# ChristmasTree.net
KiCad netlist of a schematic drawn in EAGLE
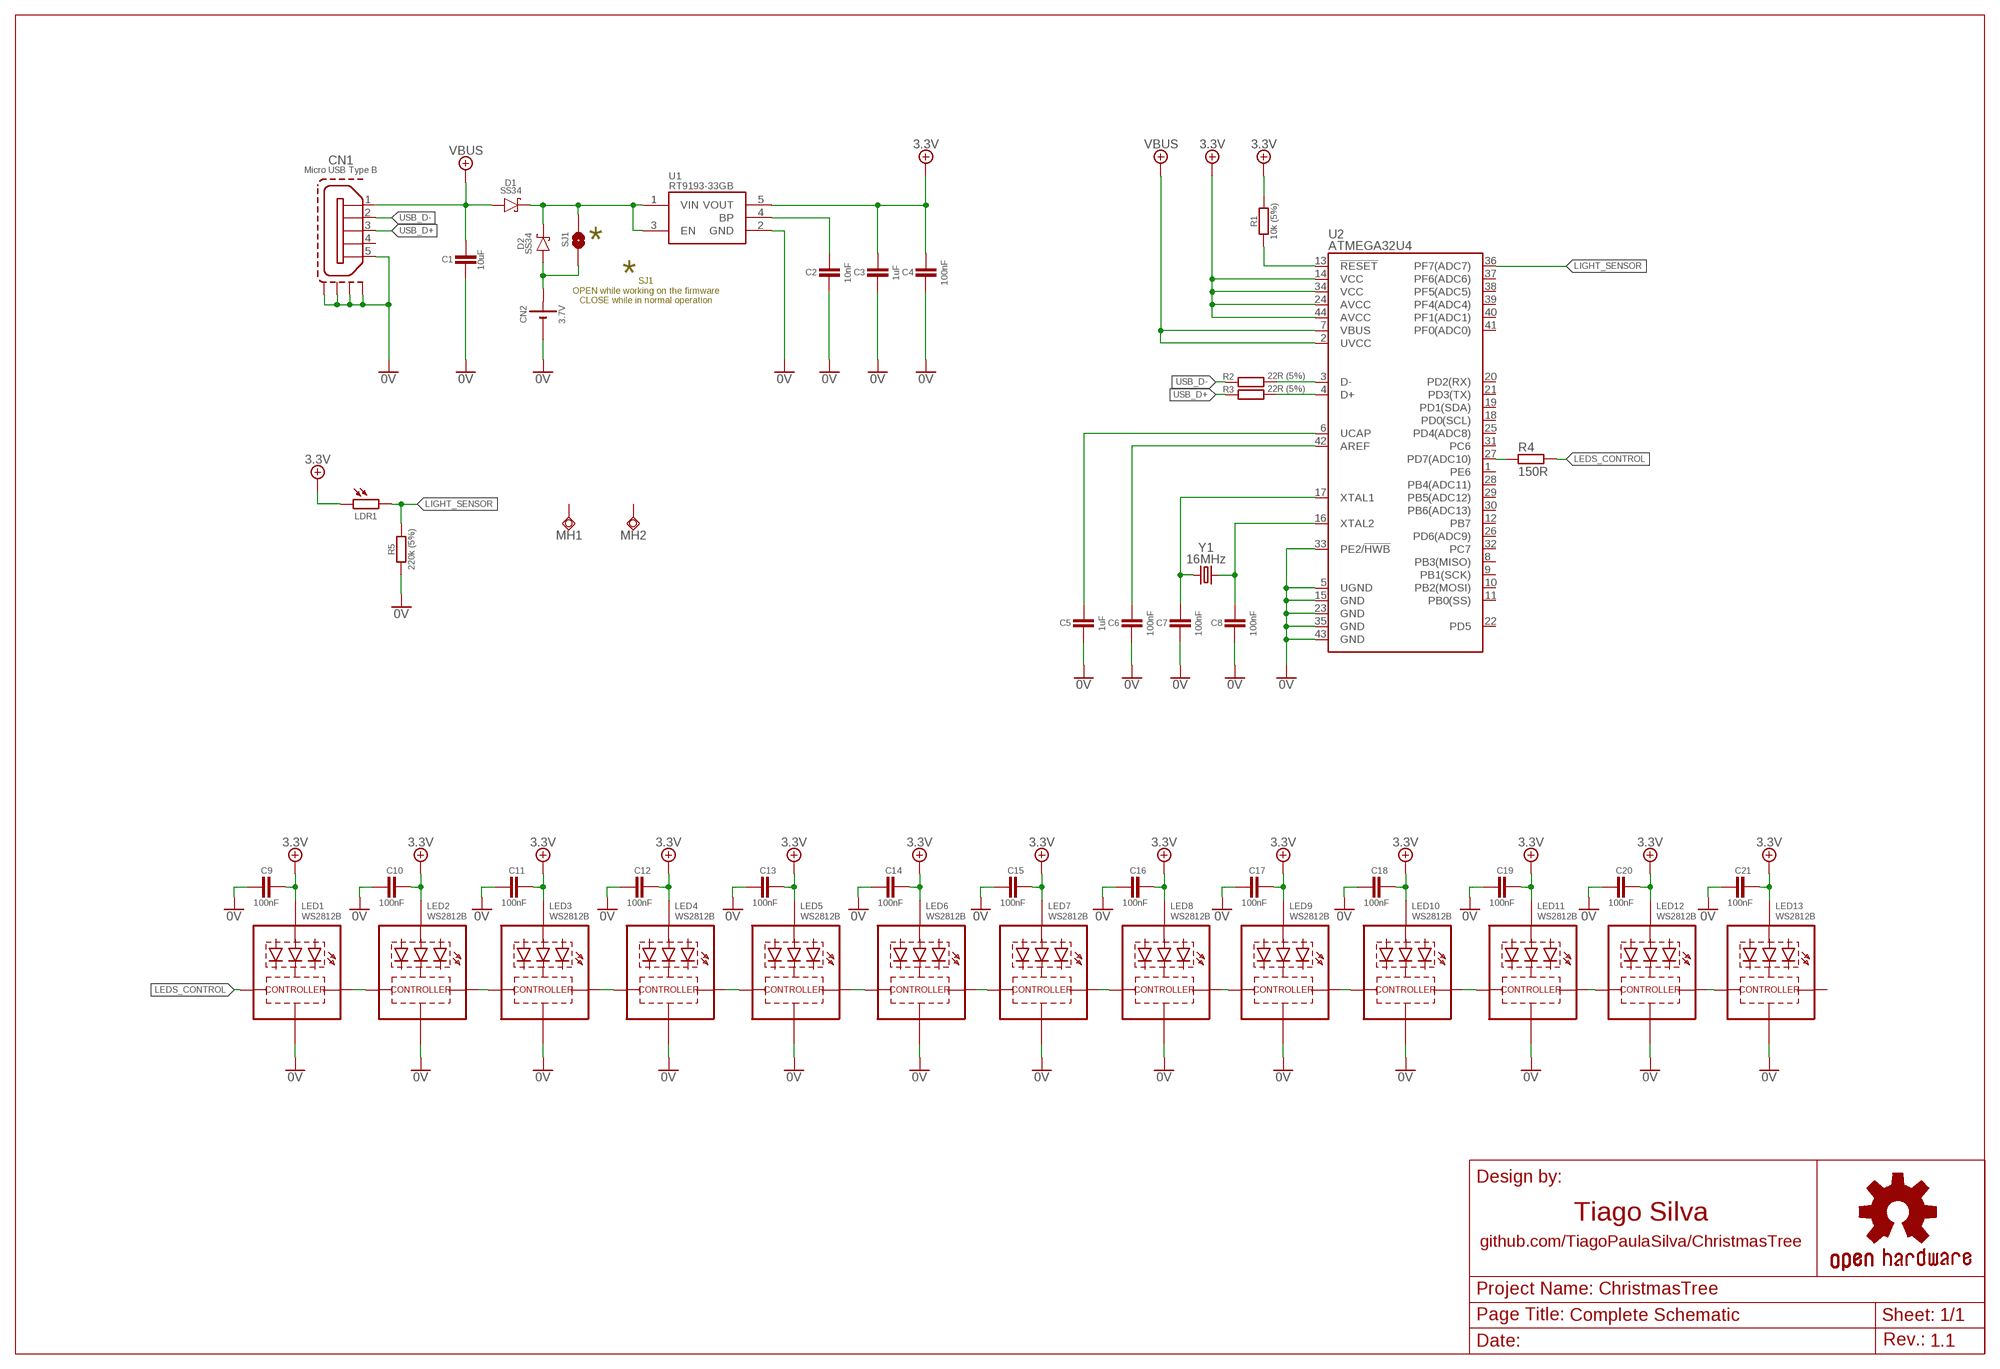
[diagram p0: schematic, sheet 1]

(export (version "E")
  (design (tool "Eeschema 10.0.6"))
  (components
    (comp (ref "C1")
      (value "10uF")
      (footprint "eagle-import:C0805")
      (libsource (lib "eagle-import") (part "C_0805"))
    )
    (comp (ref "C2")
      (value "10nF")
      (footprint "eagle-import:C0603")
      (libsource (lib "eagle-import") (part "C_0603"))
    )
    (comp (ref "C3")
      (value "1uF")
      (footprint "eagle-import:C0603")
      (libsource (lib "eagle-import") (part "C_0603"))
    )
    (comp (ref "C4")
      (value "100nF")
      (footprint "eagle-import:C0603")
      (libsource (lib "eagle-import") (part "C_0603"))
    )
    (comp (ref "C5")
      (value "1uF")
      (footprint "eagle-import:C0603")
      (libsource (lib "eagle-import") (part "C_0603"))
    )
    (comp (ref "C6")
      (value "100nF")
      (footprint "eagle-import:C0603")
      (libsource (lib "eagle-import") (part "C_0603"))
    )
    (comp (ref "C7")
      (value "100nF")
      (footprint "eagle-import:C0603")
      (libsource (lib "eagle-import") (part "C_0603"))
    )
    (comp (ref "C8")
      (value "100nF")
      (footprint "eagle-import:C0603")
      (libsource (lib "eagle-import") (part "C_0603"))
    )
    (comp (ref "C9")
      (value "100nF")
      (footprint "eagle-import:C0603")
      (libsource (lib "eagle-import") (part "C_0603"))
    )
    (comp (ref "C10")
      (value "100nF")
      (footprint "eagle-import:C0603")
      (libsource (lib "eagle-import") (part "C_0603"))
    )
    (comp (ref "C11")
      (value "100nF")
      (footprint "eagle-import:C0603")
      (libsource (lib "eagle-import") (part "C_0603"))
    )
    (comp (ref "C12")
      (value "100nF")
      (footprint "eagle-import:C0603")
      (libsource (lib "eagle-import") (part "C_0603"))
    )
    (comp (ref "C13")
      (value "100nF")
      (footprint "eagle-import:C0603")
      (libsource (lib "eagle-import") (part "C_0603"))
    )
    (comp (ref "C14")
      (value "100nF")
      (footprint "eagle-import:C0603")
      (libsource (lib "eagle-import") (part "C_0603"))
    )
    (comp (ref "C15")
      (value "100nF")
      (footprint "eagle-import:C0603")
      (libsource (lib "eagle-import") (part "C_0603"))
    )
    (comp (ref "C16")
      (value "100nF")
      (footprint "eagle-import:C0603")
      (libsource (lib "eagle-import") (part "C_0603"))
    )
    (comp (ref "C17")
      (value "100nF")
      (footprint "eagle-import:C0603")
      (libsource (lib "eagle-import") (part "C_0603"))
    )
    (comp (ref "C18")
      (value "100nF")
      (footprint "eagle-import:C0603")
      (libsource (lib "eagle-import") (part "C_0603"))
    )
    (comp (ref "C19")
      (value "100nF")
      (footprint "eagle-import:C0603")
      (libsource (lib "eagle-import") (part "C_0603"))
    )
    (comp (ref "C20")
      (value "100nF")
      (footprint "eagle-import:C0603")
      (libsource (lib "eagle-import") (part "C_0603"))
    )
    (comp (ref "C21")
      (value "100nF")
      (footprint "eagle-import:C0603")
      (libsource (lib "eagle-import") (part "C_0603"))
    )
    (comp (ref "CN1")
      (value "Micro USB Type B")
      (footprint "eagle-import:10118193-0001LF")
      (libsource (lib "eagle-import") (part "MICRO-USB"))
    )
    (comp (ref "CN2")
      (value "3.7V")
      (footprint "eagle-import:JST-PH2")
      (libsource (lib "eagle-import") (part "CELL-CONNECTOR"))
    )
    (comp (ref "D1")
      (value "SS34")
      (footprint "eagle-import:DO214AB")
      (libsource (lib "eagle-import") (part "SS34"))
    )
    (comp (ref "D2")
      (value "SS34")
      (footprint "eagle-import:DO214AB")
      (libsource (lib "eagle-import") (part "SS34"))
    )
    (comp (ref "LDR1")
      (value "A1050_09")
      (footprint "eagle-import:T0-46-A10XX")
      (libsource (lib "eagle-import") (part "A1050_09"))
    )
    (comp (ref "LED1")
      (value "WS2812B")
      (footprint "eagle-import:5050")
      (libsource (lib "eagle-import") (part "WS2812B"))
    )
    (comp (ref "LED2")
      (value "WS2812B")
      (footprint "eagle-import:5050")
      (libsource (lib "eagle-import") (part "WS2812B"))
    )
    (comp (ref "LED3")
      (value "WS2812B")
      (footprint "eagle-import:5050")
      (libsource (lib "eagle-import") (part "WS2812B"))
    )
    (comp (ref "LED4")
      (value "WS2812B")
      (footprint "eagle-import:5050")
      (libsource (lib "eagle-import") (part "WS2812B"))
    )
    (comp (ref "LED5")
      (value "WS2812B")
      (footprint "eagle-import:5050")
      (libsource (lib "eagle-import") (part "WS2812B"))
    )
    (comp (ref "LED6")
      (value "WS2812B")
      (footprint "eagle-import:5050")
      (libsource (lib "eagle-import") (part "WS2812B"))
    )
    (comp (ref "LED7")
      (value "WS2812B")
      (footprint "eagle-import:5050")
      (libsource (lib "eagle-import") (part "WS2812B"))
    )
    (comp (ref "LED8")
      (value "WS2812B")
      (footprint "eagle-import:5050")
      (libsource (lib "eagle-import") (part "WS2812B"))
    )
    (comp (ref "LED9")
      (value "WS2812B")
      (footprint "eagle-import:5050")
      (libsource (lib "eagle-import") (part "WS2812B"))
    )
    (comp (ref "LED10")
      (value "WS2812B")
      (footprint "eagle-import:5050")
      (libsource (lib "eagle-import") (part "WS2812B"))
    )
    (comp (ref "LED11")
      (value "WS2812B")
      (footprint "eagle-import:5050")
      (libsource (lib "eagle-import") (part "WS2812B"))
    )
    (comp (ref "LED12")
      (value "WS2812B")
      (footprint "eagle-import:5050")
      (libsource (lib "eagle-import") (part "WS2812B"))
    )
    (comp (ref "LED13")
      (value "WS2812B")
      (footprint "eagle-import:5050")
      (libsource (lib "eagle-import") (part "WS2812B"))
    )
    (comp (ref "MH1")
      (value "TPSQTP20R")
      (footprint "eagle-import:TP20R")
      (libsource (lib "eagle-import") (part "TPSQTP20R"))
    )
    (comp (ref "MH2")
      (value "TPSQTP20R")
      (footprint "eagle-import:TP20R")
      (libsource (lib "eagle-import") (part "TPSQTP20R"))
    )
    (comp (ref "R1")
      (value "10k (5%)")
      (footprint "eagle-import:R0603")
      (libsource (lib "eagle-import") (part "R_0603"))
    )
    (comp (ref "R2")
      (value "22R (5%)")
      (footprint "eagle-import:R0603")
      (libsource (lib "eagle-import") (part "R_0603"))
    )
    (comp (ref "R3")
      (value "22R (5%)")
      (footprint "eagle-import:R0603")
      (libsource (lib "eagle-import") (part "R_0603"))
    )
    (comp (ref "R4")
      (value "150R")
      (footprint "eagle-import:R0603")
      (libsource (lib "eagle-import") (part "R_0603"))
    )
    (comp (ref "R5")
      (value "220k (5%)")
      (footprint "eagle-import:R0603")
      (libsource (lib "eagle-import") (part "R_0603"))
    )
    (comp (ref "SJ1") (value "SJ") (footprint "eagle-import:SJ") (libsource (lib "eagle-import") (part "SJ")))
    (comp (ref "U1")
      (value "RT9193-33GB")
      (footprint "eagle-import:SOT94P279X129-5N")
      (fields (field (name "MF") "Richtek USA"))
      (libsource (lib "eagle-import") (part "RT9193-33GB"))
    )
    (comp (ref "U2")
      (value "ATMEGA32U4")
      (footprint "eagle-import:TESTING_QFN-44")
      (libsource (lib "eagle-import") (part "TESTING_ATMEGA32U4QFN"))
    )
    (comp (ref "Y1")
      (value "16MHz")
      (footprint "eagle-import:5.0X3.2_KX-9A")
      (libsource (lib "eagle-import") (part "KX-9A"))
    )
  )
  (nets
    (net (code "1") (name "0V") (class "Default")
      (node (ref "C1") (pin "2") (pinfunction "2_2") (pintype "passive"))
      (node (ref "C10") (pin "2") (pinfunction "2_2") (pintype "passive"))
      (node (ref "C11") (pin "2") (pinfunction "2_2") (pintype "passive"))
      (node (ref "C12") (pin "2") (pinfunction "2_2") (pintype "passive"))
      (node (ref "C13") (pin "2") (pinfunction "2_2") (pintype "passive"))
      (node (ref "C14") (pin "2") (pinfunction "2_2") (pintype "passive"))
      (node (ref "C15") (pin "2") (pinfunction "2_2") (pintype "passive"))
      (node (ref "C16") (pin "2") (pinfunction "2_2") (pintype "passive"))
      (node (ref "C17") (pin "2") (pinfunction "2_2") (pintype "passive"))
      (node (ref "C18") (pin "2") (pinfunction "2_2") (pintype "passive"))
      (node (ref "C19") (pin "2") (pinfunction "2_2") (pintype "passive"))
      (node (ref "C2") (pin "2") (pinfunction "2_2") (pintype "passive"))
      (node (ref "C20") (pin "2") (pinfunction "2_2") (pintype "passive"))
      (node (ref "C21") (pin "2") (pinfunction "2_2") (pintype "passive"))
      (node (ref "C3") (pin "2") (pinfunction "2_2") (pintype "passive"))
      (node (ref "C4") (pin "2") (pinfunction "2_2") (pintype "passive"))
      (node (ref "C5") (pin "2") (pinfunction "2_2") (pintype "passive"))
      (node (ref "C6") (pin "2") (pinfunction "2_2") (pintype "passive"))
      (node (ref "C7") (pin "2") (pinfunction "2_2") (pintype "passive"))
      (node (ref "C8") (pin "2") (pinfunction "2_2") (pintype "passive"))
      (node (ref "C9") (pin "2") (pinfunction "2_2") (pintype "passive"))
      (node (ref "CN1") (pin "5") (pinfunction "5_5") (pintype "passive"))
      (node (ref "CN1") (pin "MP1") (pinfunction "S1_MP1") (pintype "passive"))
      (node (ref "CN1") (pin "MP2") (pinfunction "S2_MP2") (pintype "passive"))
      (node (ref "CN1") (pin "MP3") (pinfunction "S3_MP3") (pintype "passive"))
      (node (ref "CN1") (pin "MP4") (pinfunction "S4_MP4") (pintype "passive"))
      (node (ref "CN2") (pin "2") (pinfunction "-_2") (pintype "passive"))
      (node (ref "LED1") (pin "3-GND") (pinfunction "GND_3-GND") (pintype "power_in"))
      (node (ref "LED10") (pin "3-GND") (pinfunction "GND_3-GND") (pintype "power_in"))
      (node (ref "LED11") (pin "3-GND") (pinfunction "GND_3-GND") (pintype "power_in"))
      (node (ref "LED12") (pin "3-GND") (pinfunction "GND_3-GND") (pintype "power_in"))
      (node (ref "LED13") (pin "3-GND") (pinfunction "GND_3-GND") (pintype "power_in"))
      (node (ref "LED2") (pin "3-GND") (pinfunction "GND_3-GND") (pintype "power_in"))
      (node (ref "LED3") (pin "3-GND") (pinfunction "GND_3-GND") (pintype "power_in"))
      (node (ref "LED4") (pin "3-GND") (pinfunction "GND_3-GND") (pintype "power_in"))
      (node (ref "LED5") (pin "3-GND") (pinfunction "GND_3-GND") (pintype "power_in"))
      (node (ref "LED6") (pin "3-GND") (pinfunction "GND_3-GND") (pintype "power_in"))
      (node (ref "LED7") (pin "3-GND") (pinfunction "GND_3-GND") (pintype "power_in"))
      (node (ref "LED8") (pin "3-GND") (pinfunction "GND_3-GND") (pintype "power_in"))
      (node (ref "LED9") (pin "3-GND") (pinfunction "GND_3-GND") (pintype "power_in"))
      (node (ref "R5") (pin "1") (pinfunction "1_1") (pintype "passive"))
      (node (ref "U1") (pin "2") (pinfunction "GND_2") (pintype "power_in"))
      (node (ref "U2") (pin "15") (pinfunction "GND_15") (pintype "bidirectional"))
      (node (ref "U2") (pin "23") (pinfunction "GND_23") (pintype "bidirectional"))
      (node (ref "U2") (pin "33") (pinfunction "PE2/~{HWB}_33") (pintype "bidirectional"))
      (node (ref "U2") (pin "35") (pinfunction "GND_35") (pintype "bidirectional"))
      (node (ref "U2") (pin "43") (pinfunction "GND_43") (pintype "bidirectional"))
      (node (ref "U2") (pin "5") (pinfunction "UGND_5") (pintype "bidirectional"))
    )
    (net (code "2") (name "3.3V") (class "Default")
      (node (ref "C10") (pin "1") (pinfunction "1_1") (pintype "passive"))
      (node (ref "C11") (pin "1") (pinfunction "1_1") (pintype "passive"))
      (node (ref "C12") (pin "1") (pinfunction "1_1") (pintype "passive"))
      (node (ref "C13") (pin "1") (pinfunction "1_1") (pintype "passive"))
      (node (ref "C14") (pin "1") (pinfunction "1_1") (pintype "passive"))
      (node (ref "C15") (pin "1") (pinfunction "1_1") (pintype "passive"))
      (node (ref "C16") (pin "1") (pinfunction "1_1") (pintype "passive"))
      (node (ref "C17") (pin "1") (pinfunction "1_1") (pintype "passive"))
      (node (ref "C18") (pin "1") (pinfunction "1_1") (pintype "passive"))
      (node (ref "C19") (pin "1") (pinfunction "1_1") (pintype "passive"))
      (node (ref "C20") (pin "1") (pinfunction "1_1") (pintype "passive"))
      (node (ref "C21") (pin "1") (pinfunction "1_1") (pintype "passive"))
      (node (ref "C3") (pin "1") (pinfunction "1_1") (pintype "passive"))
      (node (ref "C4") (pin "1") (pinfunction "1_1") (pintype "passive"))
      (node (ref "C9") (pin "1") (pinfunction "1_1") (pintype "passive"))
      (node (ref "LDR1") (pin "1") (pinfunction "1_1") (pintype "passive"))
      (node (ref "LED1") (pin "1-VDD") (pinfunction "VDD_1-VDD") (pintype "power_in"))
      (node (ref "LED10") (pin "1-VDD") (pinfunction "VDD_1-VDD") (pintype "power_in"))
      (node (ref "LED11") (pin "1-VDD") (pinfunction "VDD_1-VDD") (pintype "power_in"))
      (node (ref "LED12") (pin "1-VDD") (pinfunction "VDD_1-VDD") (pintype "power_in"))
      (node (ref "LED13") (pin "1-VDD") (pinfunction "VDD_1-VDD") (pintype "power_in"))
      (node (ref "LED2") (pin "1-VDD") (pinfunction "VDD_1-VDD") (pintype "power_in"))
      (node (ref "LED3") (pin "1-VDD") (pinfunction "VDD_1-VDD") (pintype "power_in"))
      (node (ref "LED4") (pin "1-VDD") (pinfunction "VDD_1-VDD") (pintype "power_in"))
      (node (ref "LED5") (pin "1-VDD") (pinfunction "VDD_1-VDD") (pintype "power_in"))
      (node (ref "LED6") (pin "1-VDD") (pinfunction "VDD_1-VDD") (pintype "power_in"))
      (node (ref "LED7") (pin "1-VDD") (pinfunction "VDD_1-VDD") (pintype "power_in"))
      (node (ref "LED8") (pin "1-VDD") (pinfunction "VDD_1-VDD") (pintype "power_in"))
      (node (ref "LED9") (pin "1-VDD") (pinfunction "VDD_1-VDD") (pintype "power_in"))
      (node (ref "R1") (pin "2") (pinfunction "2_2") (pintype "passive"))
      (node (ref "U1") (pin "5") (pinfunction "VOUT_5") (pintype "output"))
      (node (ref "U2") (pin "14") (pinfunction "VCC_14") (pintype "bidirectional"))
      (node (ref "U2") (pin "24") (pinfunction "AVCC_24") (pintype "bidirectional"))
      (node (ref "U2") (pin "34") (pinfunction "VCC_34") (pintype "bidirectional"))
      (node (ref "U2") (pin "44") (pinfunction "AVCC_44") (pintype "bidirectional"))
    )
    (net (code "3") (name "LEDS_CONTROL") (class "Default")
      (node (ref "LED1") (pin "4-DIN") (pinfunction "DI_4-DIN") (pintype "input"))
      (node (ref "R4") (pin "2") (pinfunction "2_2") (pintype "passive"))
    )
    (net (code "4") (name "LIGHT_SENSOR") (class "Default")
      (node (ref "LDR1") (pin "2") (pinfunction "2_2") (pintype "passive"))
      (node (ref "R5") (pin "2") (pinfunction "2_2") (pintype "passive"))
      (node (ref "U2") (pin "36") (pinfunction "PF7(ADC7)_36") (pintype "bidirectional"))
    )
    (net (code "5") (name "Net-(CN2-+)") (class "Default")
      (node (ref "CN2") (pin "1") (pinfunction "+_1") (pintype "passive"))
      (node (ref "D2") (pin "A") (pinfunction "A_A") (pintype "passive"))
      (node (ref "SJ1") (pin "1") (pinfunction "1_1") (pintype "passive"))
    )
    (net (code "6") (name "Net-(D1-K)") (class "Default")
      (node (ref "D1") (pin "C") (pinfunction "K_C") (pintype "passive"))
      (node (ref "D2") (pin "C") (pinfunction "K_C") (pintype "passive"))
      (node (ref "SJ1") (pin "2") (pinfunction "2_2") (pintype "passive"))
      (node (ref "U1") (pin "1") (pinfunction "VIN_1") (pintype "input"))
      (node (ref "U1") (pin "3") (pinfunction "EN_3") (pintype "input"))
    )
    (net (code "7") (name "Net-(LED1-DO)") (class "Default")
      (node (ref "LED1") (pin "2-DOUT") (pinfunction "DO_2-DOUT") (pintype "output"))
      (node (ref "LED2") (pin "4-DIN") (pinfunction "DI_4-DIN") (pintype "input"))
    )
    (net (code "8") (name "Net-(LED2-DO)") (class "Default")
      (node (ref "LED2") (pin "2-DOUT") (pinfunction "DO_2-DOUT") (pintype "output"))
      (node (ref "LED3") (pin "4-DIN") (pinfunction "DI_4-DIN") (pintype "input"))
    )
    (net (code "9") (name "Net-(LED3-DO)") (class "Default")
      (node (ref "LED3") (pin "2-DOUT") (pinfunction "DO_2-DOUT") (pintype "output"))
      (node (ref "LED4") (pin "4-DIN") (pinfunction "DI_4-DIN") (pintype "input"))
    )
    (net (code "10") (name "Net-(LED4-DO)") (class "Default")
      (node (ref "LED4") (pin "2-DOUT") (pinfunction "DO_2-DOUT") (pintype "output"))
      (node (ref "LED5") (pin "4-DIN") (pinfunction "DI_4-DIN") (pintype "input"))
    )
    (net (code "11") (name "Net-(LED5-DO)") (class "Default")
      (node (ref "LED5") (pin "2-DOUT") (pinfunction "DO_2-DOUT") (pintype "output"))
      (node (ref "LED6") (pin "4-DIN") (pinfunction "DI_4-DIN") (pintype "input"))
    )
    (net (code "12") (name "Net-(LED6-DO)") (class "Default")
      (node (ref "LED6") (pin "2-DOUT") (pinfunction "DO_2-DOUT") (pintype "output"))
      (node (ref "LED7") (pin "4-DIN") (pinfunction "DI_4-DIN") (pintype "input"))
    )
    (net (code "13") (name "Net-(LED7-DO)") (class "Default")
      (node (ref "LED7") (pin "2-DOUT") (pinfunction "DO_2-DOUT") (pintype "output"))
      (node (ref "LED8") (pin "4-DIN") (pinfunction "DI_4-DIN") (pintype "input"))
    )
    (net (code "14") (name "Net-(LED8-DO)") (class "Default")
      (node (ref "LED8") (pin "2-DOUT") (pinfunction "DO_2-DOUT") (pintype "output"))
      (node (ref "LED9") (pin "4-DIN") (pinfunction "DI_4-DIN") (pintype "input"))
    )
    (net (code "15") (name "Net-(LED10-DI)") (class "Default")
      (node (ref "LED10") (pin "4-DIN") (pinfunction "DI_4-DIN") (pintype "input"))
      (node (ref "LED9") (pin "2-DOUT") (pinfunction "DO_2-DOUT") (pintype "output"))
    )
    (net (code "16") (name "Net-(LED10-DO)") (class "Default")
      (node (ref "LED10") (pin "2-DOUT") (pinfunction "DO_2-DOUT") (pintype "output"))
      (node (ref "LED11") (pin "4-DIN") (pinfunction "DI_4-DIN") (pintype "input"))
    )
    (net (code "17") (name "Net-(LED11-DO)") (class "Default")
      (node (ref "LED11") (pin "2-DOUT") (pinfunction "DO_2-DOUT") (pintype "output"))
      (node (ref "LED12") (pin "4-DIN") (pinfunction "DI_4-DIN") (pintype "input"))
    )
    (net (code "18") (name "Net-(LED12-DO)") (class "Default")
      (node (ref "LED12") (pin "2-DOUT") (pinfunction "DO_2-DOUT") (pintype "output"))
      (node (ref "LED13") (pin "4-DIN") (pinfunction "DI_4-DIN") (pintype "input"))
    )
    (net (code "19") (name "Net-(U1-BP)") (class "Default")
      (node (ref "C2") (pin "1") (pinfunction "1_1") (pintype "passive"))
      (node (ref "U1") (pin "4") (pinfunction "BP_4") (pintype "passive"))
    )
    (net (code "20") (name "Net-(U2-AREF)") (class "Default")
      (node (ref "C6") (pin "1") (pinfunction "1_1") (pintype "passive"))
      (node (ref "U2") (pin "42") (pinfunction "AREF_42") (pintype "bidirectional"))
    )
    (net (code "21") (name "Net-(U2-D+)") (class "Default")
      (node (ref "R3") (pin "2") (pinfunction "2_2") (pintype "passive"))
      (node (ref "U2") (pin "4") (pinfunction "D+_4") (pintype "bidirectional"))
    )
    (net (code "22") (name "Net-(U2-D-)") (class "Default")
      (node (ref "R2") (pin "2") (pinfunction "2_2") (pintype "passive"))
      (node (ref "U2") (pin "3") (pinfunction "D-_3") (pintype "bidirectional"))
    )
    (net (code "23") (name "Net-(U2-PD7(ADC10))") (class "Default")
      (node (ref "R4") (pin "1") (pinfunction "1_1") (pintype "passive"))
      (node (ref "U2") (pin "27") (pinfunction "PD7(ADC10)_27") (pintype "bidirectional"))
    )
    (net (code "24") (name "Net-(U2-UCAP)") (class "Default")
      (node (ref "C5") (pin "1") (pinfunction "1_1") (pintype "passive"))
      (node (ref "U2") (pin "6") (pinfunction "UCAP_6") (pintype "bidirectional"))
    )
    (net (code "25") (name "Net-(U2-XTAL1)") (class "Default")
      (node (ref "C7") (pin "1") (pinfunction "1_1") (pintype "passive"))
      (node (ref "U2") (pin "17") (pinfunction "XTAL1_17") (pintype "bidirectional"))
      (node (ref "Y1") (pin "1") (pinfunction "1_1") (pintype "passive"))
    )
    (net (code "26") (name "Net-(U2-XTAL2)") (class "Default")
      (node (ref "C8") (pin "1") (pinfunction "1_1") (pintype "passive"))
      (node (ref "U2") (pin "16") (pinfunction "XTAL2_16") (pintype "bidirectional"))
      (node (ref "Y1") (pin "3") (pinfunction "2_3") (pintype "passive"))
    )
    (net (code "27") (name "Net-(U2-~{RESET})") (class "Default")
      (node (ref "R1") (pin "1") (pinfunction "1_1") (pintype "passive"))
      (node (ref "U2") (pin "13") (pinfunction "~{RESET}_13") (pintype "bidirectional"))
    )
    (net (code "28") (name "USB_D+") (class "Default")
      (node (ref "CN1") (pin "3") (pinfunction "3_3") (pintype "passive"))
      (node (ref "R3") (pin "1") (pinfunction "1_1") (pintype "passive"))
    )
    (net (code "29") (name "USB_D-") (class "Default")
      (node (ref "CN1") (pin "2") (pinfunction "2_2") (pintype "passive"))
      (node (ref "R2") (pin "1") (pinfunction "1_1") (pintype "passive"))
    )
    (net (code "30") (name "VBUS") (class "Default")
      (node (ref "C1") (pin "1") (pinfunction "1_1") (pintype "passive"))
      (node (ref "CN1") (pin "1") (pinfunction "1_1") (pintype "passive"))
      (node (ref "D1") (pin "A") (pinfunction "A_A") (pintype "passive"))
      (node (ref "U2") (pin "2") (pinfunction "UVCC_2") (pintype "bidirectional"))
      (node (ref "U2") (pin "7") (pinfunction "VBUS_7") (pintype "bidirectional"))
    )
    (net (code "31") (name "unconnected-(CN1-Pad4)") (class "Default")
      (node (ref "CN1") (pin "4") (pinfunction "4_4") (pintype "passive"))
    )
    (net (code "32") (name "unconnected-(LED13-DO-Pad2-DOUT)") (class "Default")
      (node (ref "LED13") (pin "2-DOUT") (pinfunction "DO_2-DOUT") (pintype "output"))
    )
    (net (code "33") (name "unconnected-(MH1-PadTP)") (class "Default")
      (node (ref "MH1") (pin "TP") (pinfunction "TP_TP") (pintype "input"))
    )
    (net (code "34") (name "unconnected-(MH2-PadTP)") (class "Default")
      (node (ref "MH2") (pin "TP") (pinfunction "TP_TP") (pintype "input"))
    )
    (net (code "35") (name "unconnected-(U2-PB0(SS)-Pad11)") (class "Default")
      (node (ref "U2") (pin "11") (pinfunction "PB0(SS)_11") (pintype "bidirectional"))
    )
    (net (code "36") (name "unconnected-(U2-PB1(SCK)-Pad9)") (class "Default")
      (node (ref "U2") (pin "9") (pinfunction "PB1(SCK)_9") (pintype "bidirectional"))
    )
    (net (code "37") (name "unconnected-(U2-PB2(MOSI)-Pad10)") (class "Default")
      (node (ref "U2") (pin "10") (pinfunction "PB2(MOSI)_10") (pintype "bidirectional"))
    )
    (net (code "38") (name "unconnected-(U2-PB3(MISO)-Pad8)") (class "Default")
      (node (ref "U2") (pin "8") (pinfunction "PB3(MISO)_8") (pintype "bidirectional"))
    )
    (net (code "39") (name "unconnected-(U2-PB4(ADC11)-Pad28)") (class "Default")
      (node (ref "U2") (pin "28") (pinfunction "PB4(ADC11)_28") (pintype "bidirectional"))
    )
    (net (code "40") (name "unconnected-(U2-PB5(ADC12)-Pad29)") (class "Default")
      (node (ref "U2") (pin "29") (pinfunction "PB5(ADC12)_29") (pintype "bidirectional"))
    )
    (net (code "41") (name "unconnected-(U2-PB6(ADC13)-Pad30)") (class "Default")
      (node (ref "U2") (pin "30") (pinfunction "PB6(ADC13)_30") (pintype "bidirectional"))
    )
    (net (code "42") (name "unconnected-(U2-PB7-Pad12)") (class "Default")
      (node (ref "U2") (pin "12") (pinfunction "PB7_12") (pintype "bidirectional"))
    )
    (net (code "43") (name "unconnected-(U2-PC6-Pad31)") (class "Default")
      (node (ref "U2") (pin "31") (pinfunction "PC6_31") (pintype "bidirectional"))
    )
    (net (code "44") (name "unconnected-(U2-PC7-Pad32)") (class "Default")
      (node (ref "U2") (pin "32") (pinfunction "PC7_32") (pintype "bidirectional"))
    )
    (net (code "45") (name "unconnected-(U2-PD0(SCL)-Pad18)") (class "Default")
      (node (ref "U2") (pin "18") (pinfunction "PD0(SCL)_18") (pintype "bidirectional"))
    )
    (net (code "46") (name "unconnected-(U2-PD1(SDA)-Pad19)") (class "Default")
      (node (ref "U2") (pin "19") (pinfunction "PD1(SDA)_19") (pintype "bidirectional"))
    )
    (net (code "47") (name "unconnected-(U2-PD2(RX)-Pad20)") (class "Default")
      (node (ref "U2") (pin "20") (pinfunction "PD2(RX)_20") (pintype "bidirectional"))
    )
    (net (code "48") (name "unconnected-(U2-PD3(TX)-Pad21)") (class "Default")
      (node (ref "U2") (pin "21") (pinfunction "PD3(TX)_21") (pintype "bidirectional"))
    )
    (net (code "49") (name "unconnected-(U2-PD4(ADC8)-Pad25)") (class "Default")
      (node (ref "U2") (pin "25") (pinfunction "PD4(ADC8)_25") (pintype "bidirectional"))
    )
    (net (code "50") (name "unconnected-(U2-PD5-Pad22)") (class "Default")
      (node (ref "U2") (pin "22") (pinfunction "PD5_22") (pintype "bidirectional"))
    )
    (net (code "51") (name "unconnected-(U2-PD6(ADC9)-Pad26)") (class "Default")
      (node (ref "U2") (pin "26") (pinfunction "PD6(ADC9)_26") (pintype "bidirectional"))
    )
    (net (code "52") (name "unconnected-(U2-PE6-Pad1)") (class "Default")
      (node (ref "U2") (pin "1") (pinfunction "PE6_1") (pintype "bidirectional"))
    )
    (net (code "53") (name "unconnected-(U2-PF0(ADC0)-Pad41)") (class "Default")
      (node (ref "U2") (pin "41") (pinfunction "PF0(ADC0)_41") (pintype "bidirectional"))
    )
    (net (code "54") (name "unconnected-(U2-PF1(ADC1)-Pad40)") (class "Default")
      (node (ref "U2") (pin "40") (pinfunction "PF1(ADC1)_40") (pintype "bidirectional"))
    )
    (net (code "55") (name "unconnected-(U2-PF4(ADC4)-Pad39)") (class "Default")
      (node (ref "U2") (pin "39") (pinfunction "PF4(ADC4)_39") (pintype "bidirectional"))
    )
    (net (code "56") (name "unconnected-(U2-PF5(ADC5)-Pad38)") (class "Default")
      (node (ref "U2") (pin "38") (pinfunction "PF5(ADC5)_38") (pintype "bidirectional"))
    )
    (net (code "57") (name "unconnected-(U2-PF6(ADC6)-Pad37)") (class "Default")
      (node (ref "U2") (pin "37") (pinfunction "PF6(ADC6)_37") (pintype "bidirectional"))
    )
  )
)
